# AS5047D_Breakout.net
KiCad netlist of a schematic drawn in Altium Designer
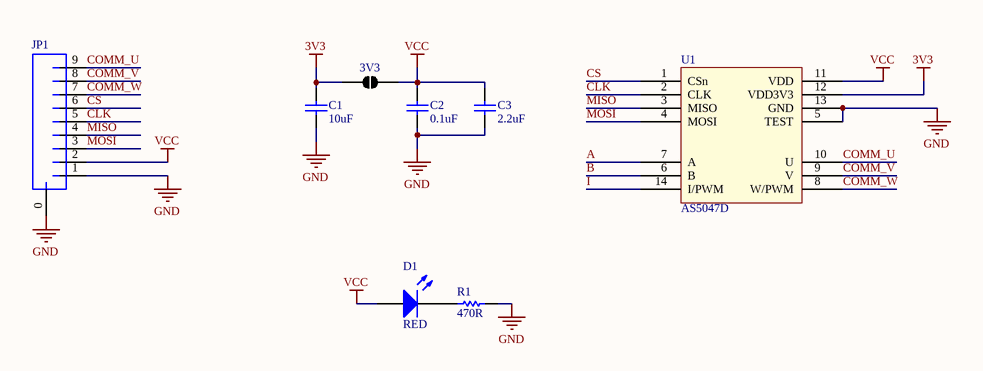
[diagram p0: AS5047D_Breakout.SchDoc]

(export (version "E")
  (design (tool "Eeschema 10.0.6"))
  (components
    (comp (ref "3V3")
      (value "Solder Jumper")
      (footprint "SOLDER JUMPER")
      (libsource (lib "Components") (part "Solder Jumper"))
    )
    (comp (ref "C1")
      (value "10uF")
      (footprint "CAPC0603(1608)100_L")
      (description "CAP 10uF 6.3V ±10% 0603 (1608 Metric) Thickness 1mm SMD")
      (fields (field (name "TOLERANCE") "Â±10%"))
      (libsource (lib "Altium Content Vault") (part "CMP-1035-02796-1"))
    )
    (comp (ref "C2")
      (value "0.1uF")
      (footprint "CAPC0603(1608)100_L")
      (description "CAP 100nF 50V ±5% 0603 (1608 Metric) Thickness 1mm SMD")
      (fields (field (name "TOLERANCE") "Â±5%"))
      (libsource (lib "Altium Content Vault") (part "CMP-1035-02591-1"))
    )
    (comp (ref "C3")
      (value "2.2uF")
      (footprint "CAPC0603(1608)100_L")
      (description "CAP 2.2uF 25V ±10% 0603 (1608 Metric) Thickness 1mm SMD")
      (fields (field (name "TOLERANCE") "Â±10%"))
      (libsource (lib "Altium Content Vault") (part "CMP-1035-02767-1"))
    )
    (comp (ref "D1")
      (value "RED")
      (footprint "0603_A")
      (description "SMD mono-color Chip LED, WL-SMCW, Red")
      (fields (field (name "MANUFACTURER") "Wuerth Elektronik") (field (name "PARTNUMBER") "150060RS75000"))
      (libsource (lib "Altium Content Vault") (part "CMP-1426-00001-1"))
    )
    (comp (ref "JP1")
      (value "~")
      (footprint "JST-9-SMD-RIGHT-ANGLE")
      (fields (field (name "MANUFACTURER") "JST Sales America Inc."))
      (libsource (lib "Components") (part "JST-9-SMD-RIGHT-ANGLE"))
    )
    (comp (ref "R1")
      (value "470R")
      (footprint "RESC0603(1608)_L")
      (description "470R 0.1W 5% 0603 (1608 Metric)  SMD")
      (fields (field (name "TOLERANCE") "5 %") (field (name "POWER") "0.1 W"))
      (libsource (lib "Altium Content Vault") (part "CMP-1012-00066-1"))
    )
    (comp (ref "U1") (value "AS5047D") (footprint "TSSOP-14") (libsource (lib "Components") (part "AS5047D")))
  )
  (nets
    (net (code "1") (name "/A") (class "Default")
      (node (ref "U1") (pin "7") (pinfunction "A_7") (pintype "passive"))
    )
    (net (code "2") (name "/B") (class "Default")
      (node (ref "U1") (pin "6") (pinfunction "B_6") (pintype "passive"))
    )
    (net (code "3") (name "/CLK") (class "Default")
      (node (ref "JP1") (pin "5") (pinfunction "5_5") (pintype "passive"))
      (node (ref "U1") (pin "2") (pinfunction "CLK_2") (pintype "passive"))
    )
    (net (code "4") (name "/COMM_U") (class "Default")
      (node (ref "JP1") (pin "9") (pinfunction "9_9") (pintype "passive"))
      (node (ref "U1") (pin "10") (pinfunction "U_10") (pintype "passive"))
    )
    (net (code "5") (name "/COMM_V") (class "Default")
      (node (ref "JP1") (pin "8") (pinfunction "8_8") (pintype "passive"))
      (node (ref "U1") (pin "9") (pinfunction "V_9") (pintype "passive"))
    )
    (net (code "6") (name "/COMM_W") (class "Default")
      (node (ref "JP1") (pin "7") (pinfunction "7_7") (pintype "passive"))
      (node (ref "U1") (pin "8") (pinfunction "W/PWM_8") (pintype "passive"))
    )
    (net (code "7") (name "/CS") (class "Default")
      (node (ref "JP1") (pin "6") (pinfunction "6_6") (pintype "passive"))
      (node (ref "U1") (pin "1") (pinfunction "CSn_1") (pintype "passive"))
    )
    (net (code "8") (name "/I") (class "Default")
      (node (ref "U1") (pin "14") (pinfunction "I/PWM_14") (pintype "passive"))
    )
    (net (code "9") (name "/MISO") (class "Default")
      (node (ref "JP1") (pin "4") (pinfunction "4_4") (pintype "passive"))
      (node (ref "U1") (pin "3") (pinfunction "MISO_3") (pintype "passive"))
    )
    (net (code "10") (name "/MOSI") (class "Default")
      (node (ref "JP1") (pin "3") (pinfunction "3_3") (pintype "passive"))
      (node (ref "U1") (pin "4") (pinfunction "MOSI_4") (pintype "passive"))
    )
    (net (code "11") (name "3V3") (class "Default")
      (node (ref "3V3") (pin "2") (pinfunction "2_2") (pintype "passive"))
      (node (ref "C1") (pin "1") (pinfunction "1_1") (pintype "passive"))
      (node (ref "U1") (pin "12") (pinfunction "VDD3V3_12") (pintype "passive"))
    )
    (net (code "12") (name "GND") (class "Default")
      (node (ref "C1") (pin "2") (pinfunction "2_2") (pintype "passive"))
      (node (ref "C2") (pin "1") (pinfunction "1_1") (pintype "passive"))
      (node (ref "C3") (pin "1") (pinfunction "1_1") (pintype "passive"))
      (node (ref "JP1") (pin "0") (pinfunction "0_0") (pintype "passive"))
      (node (ref "JP1") (pin "1") (pinfunction "1_1") (pintype "passive"))
      (node (ref "R1") (pin "1") (pinfunction "1_1") (pintype "passive"))
      (node (ref "U1") (pin "13") (pinfunction "GND_13") (pintype "passive"))
      (node (ref "U1") (pin "5") (pinfunction "TEST_5") (pintype "passive"))
    )
    (net (code "13") (name "Net-(D1-K)") (class "Default")
      (node (ref "D1") (pin "1") (pinfunction "K_1") (pintype "passive"))
      (node (ref "R1") (pin "2") (pinfunction "2_2") (pintype "passive"))
    )
    (net (code "14") (name "VCC") (class "Default")
      (node (ref "3V3") (pin "1") (pinfunction "1_1") (pintype "passive"))
      (node (ref "C2") (pin "2") (pinfunction "2_2") (pintype "passive"))
      (node (ref "C3") (pin "2") (pinfunction "2_2") (pintype "passive"))
      (node (ref "D1") (pin "2") (pinfunction "A_2") (pintype "passive"))
      (node (ref "JP1") (pin "2") (pinfunction "2_2") (pintype "passive"))
      (node (ref "U1") (pin "11") (pinfunction "VDD_11") (pintype "passive"))
    )
  )
)
